# Particle-Photon-Carrier.net
KiCad netlist of a schematic drawn in EAGLE
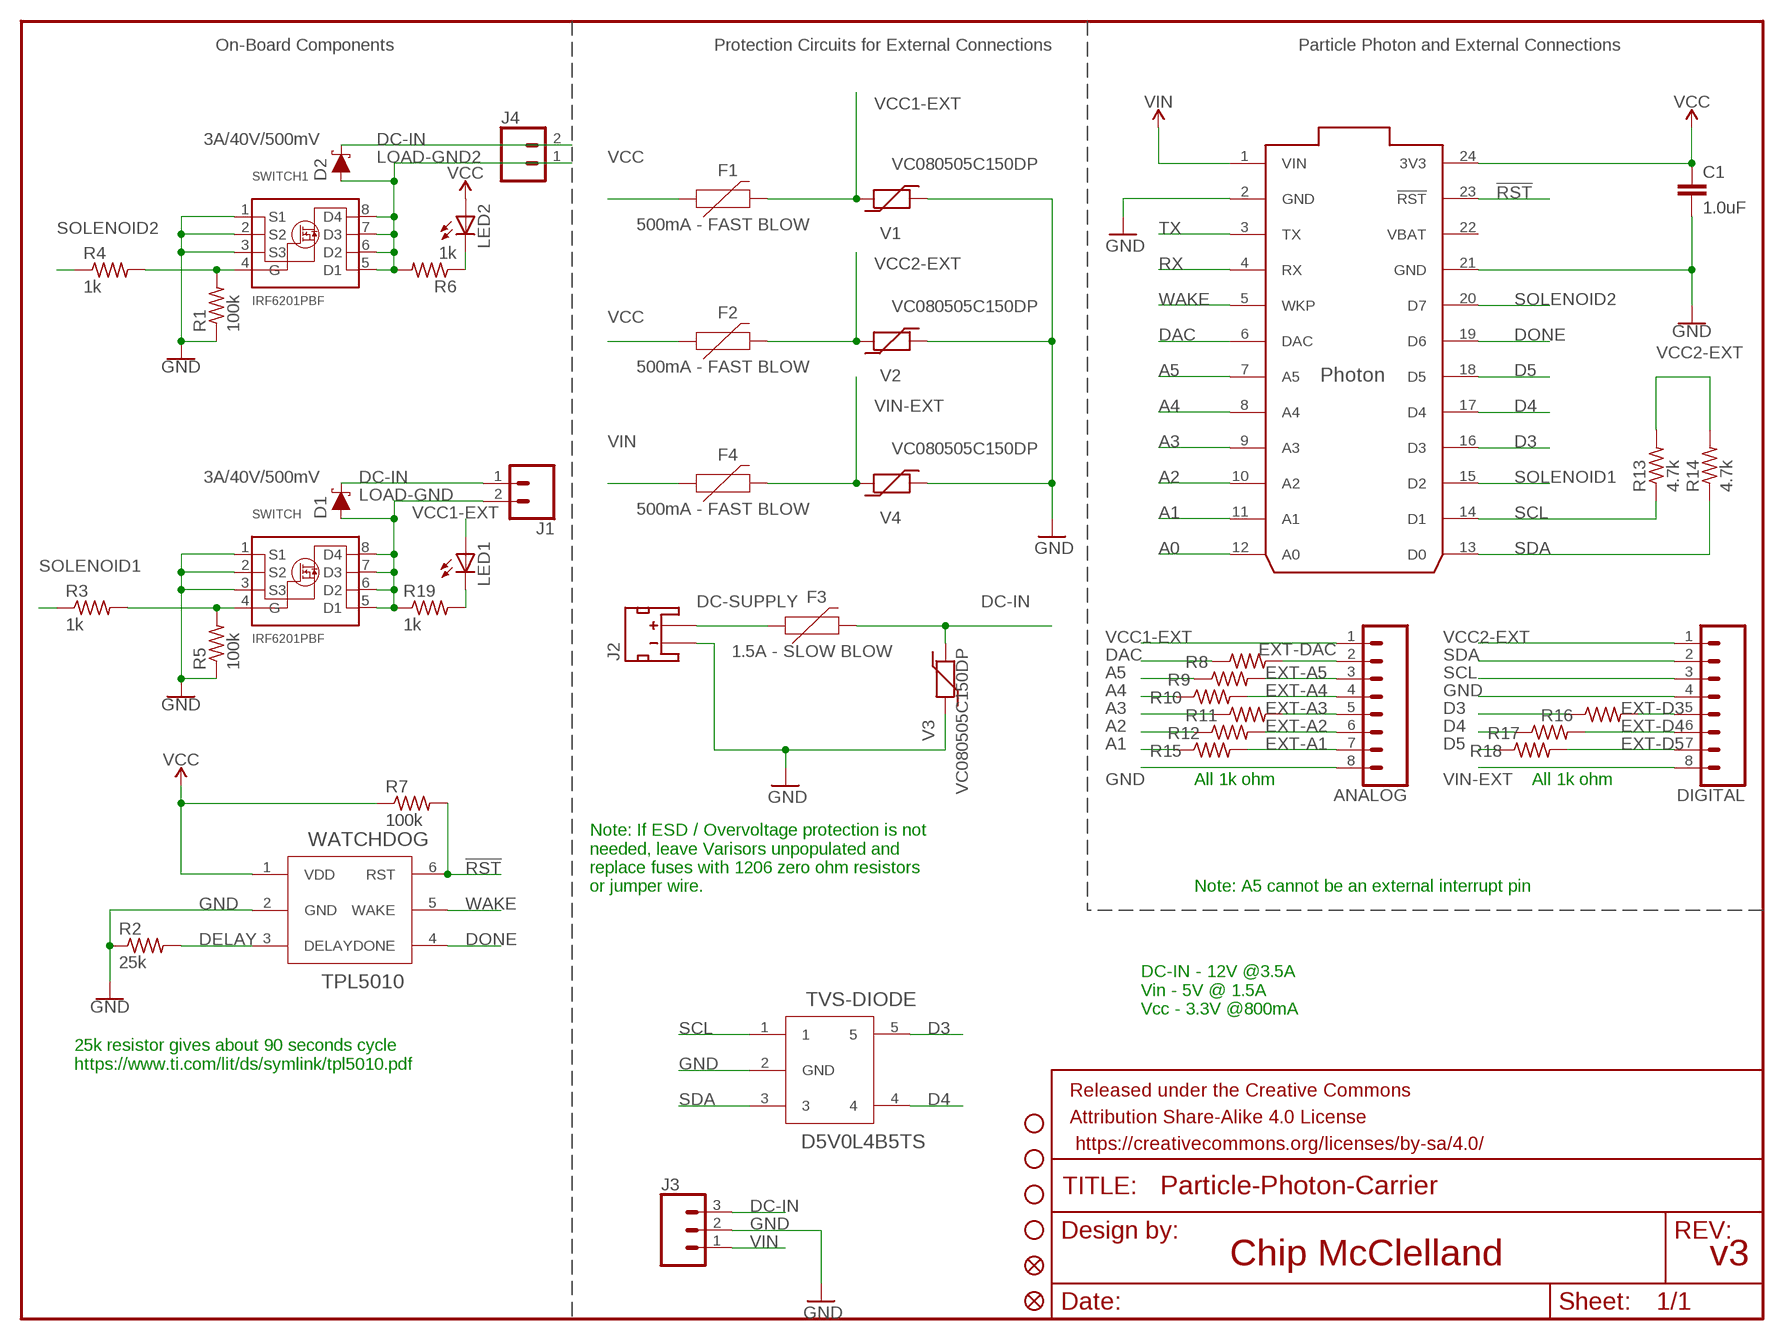
[diagram p0: schematic, sheet 1]

(export (version "E")
  (design (tool "Eeschema 10.0.6"))
  (components
    (comp (ref "ANALOG")
      (value "CONN_083.5MM-8")
      (footprint "eagle-import:SCREWTERMINAL-3.5MM-8")
      (libsource (lib "eagle-import") (part "CONN_083.5MM-8"))
    )
    (comp (ref "C1")
      (value "1.0uF")
      (footprint "eagle-import:0805")
      (libsource (lib "eagle-import") (part "1.0UF-0805-25V-10%"))
    )
    (comp (ref "D1")
      (value "3A/40V/500mV")
      (footprint "eagle-import:SMA-DIODE")
      (libsource (lib "eagle-import") (part "DIODE-SCHOTTKY-B340A"))
    )
    (comp (ref "D2")
      (value "3A/40V/500mV")
      (footprint "eagle-import:SMA-DIODE")
      (libsource (lib "eagle-import") (part "DIODE-SCHOTTKY-B340A"))
    )
    (comp (ref "DIGITAL")
      (value "CONN_083.5MM-8")
      (footprint "eagle-import:SCREWTERMINAL-3.5MM-8")
      (libsource (lib "eagle-import") (part "CONN_083.5MM-8"))
    )
    (comp (ref "F1")
      (value "500mA - FAST BLOW")
      (footprint "eagle-import:1206")
      (libsource (lib "eagle-import") (part "PPTC_HALF-AMP"))
    )
    (comp (ref "F2")
      (value "500mA - FAST BLOW")
      (footprint "eagle-import:1206")
      (libsource (lib "eagle-import") (part "PPTC_HALF-AMP"))
    )
    (comp (ref "F3")
      (value "1.5A - SLOW BLOW")
      (footprint "eagle-import:1206")
      (libsource (lib "eagle-import") (part "PPTC_HALF-AMP"))
    )
    (comp (ref "F4")
      (value "500mA - FAST BLOW")
      (footprint "eagle-import:1206")
      (libsource (lib "eagle-import") (part "PPTC_HALF-AMP"))
    )
    (comp (ref "FD1")
      (value "FIDUCIALUFIDUCIAL")
      (footprint "eagle-import:FIDUCIAL-MICRO")
      (libsource (lib "eagle-import") (part "FIDUCIALUFIDUCIAL"))
    )
    (comp (ref "FD2")
      (value "FIDUCIALUFIDUCIAL")
      (footprint "eagle-import:FIDUCIAL-MICRO")
      (libsource (lib "eagle-import") (part "FIDUCIALUFIDUCIAL"))
    )
    (comp (ref "FRAME1")
      (value "FRAME-LETTER")
      (footprint "eagle-import:CREATIVE_COMMONS")
      (libsource (lib "eagle-import") (part "FRAME-LETTER"))
    )
    (comp (ref "J1")
      (value "CONN_023.5MM")
      (footprint "eagle-import:SCREWTERMINAL-3.5MM-2")
      (libsource (lib "eagle-import") (part "CONN_023.5MM"))
    )
    (comp (ref "J2")
      (value "5V @ 2A")
      (footprint "eagle-import:JST-2-SMD")
      (libsource (lib "eagle-import") (part "JST_2MM_MALE"))
    )
    (comp (ref "J3")
      (value "CONN_03LOCK")
      (footprint "eagle-import:1X03_LOCK")
      (libsource (lib "eagle-import") (part "CONN_03LOCK"))
    )
    (comp (ref "J4")
      (value "CONN_023.5MM")
      (footprint "eagle-import:SCREWTERMINAL-3.5MM-2")
      (libsource (lib "eagle-import") (part "CONN_023.5MM"))
    )
    (comp (ref "JP3")
      (value "STAND-OFF")
      (footprint "eagle-import:STAND-OFF")
      (libsource (lib "eagle-import") (part "STAND-OFF"))
    )
    (comp (ref "JP4")
      (value "STAND-OFF")
      (footprint "eagle-import:STAND-OFF")
      (libsource (lib "eagle-import") (part "STAND-OFF"))
    )
    (comp (ref "JP5")
      (value "STAND-OFF")
      (footprint "eagle-import:STAND-OFF")
      (libsource (lib "eagle-import") (part "STAND-OFF"))
    )
    (comp (ref "JP6")
      (value "STAND-OFF")
      (footprint "eagle-import:STAND-OFF")
      (libsource (lib "eagle-import") (part "STAND-OFF"))
    )
    (comp (ref "LED1")
      (value "LEDCHIPLED_0805")
      (footprint "eagle-import:CHIPLED_0805")
      (libsource (lib "eagle-import") (part "LEDCHIPLED_0805"))
    )
    (comp (ref "LED2")
      (value "LEDCHIPLED_0805")
      (footprint "eagle-import:CHIPLED_0805")
      (libsource (lib "eagle-import") (part "LEDCHIPLED_0805"))
    )
    (comp (ref "PHOTON")
      (value "PHOTON_WITH_HEADERS")
      (footprint "eagle-import:PHOTON")
      (libsource (lib "eagle-import") (part "PHOTON_WITH_HEADERS"))
    )
    (comp (ref "R1")
      (value "100k")
      (footprint "eagle-import:R0805")
      (libsource (lib "eagle-import") (part "R-US_R0805"))
    )
    (comp (ref "R2")
      (value "25k")
      (footprint "eagle-import:R0805")
      (libsource (lib "eagle-import") (part "R-US_R0805"))
    )
    (comp (ref "R3")
      (value "1k")
      (footprint "eagle-import:R0805")
      (libsource (lib "eagle-import") (part "R-US_R0805"))
    )
    (comp (ref "R4")
      (value "1k")
      (footprint "eagle-import:R0805")
      (libsource (lib "eagle-import") (part "R-US_R0805"))
    )
    (comp (ref "R5")
      (value "100k")
      (footprint "eagle-import:R0805")
      (libsource (lib "eagle-import") (part "R-US_R0805"))
    )
    (comp (ref "R6")
      (value "1k")
      (footprint "eagle-import:R0805")
      (libsource (lib "eagle-import") (part "R-US_R0805"))
    )
    (comp (ref "R7")
      (value "100k")
      (footprint "eagle-import:R0805")
      (libsource (lib "eagle-import") (part "R-US_R0805"))
    )
    (comp (ref "R8")
      (value "1k")
      (footprint "eagle-import:R0805")
      (libsource (lib "eagle-import") (part "R-US_R0805"))
    )
    (comp (ref "R9")
      (value "1k")
      (footprint "eagle-import:R0805")
      (libsource (lib "eagle-import") (part "R-US_R0805"))
    )
    (comp (ref "R10")
      (value "1k")
      (footprint "eagle-import:R0805")
      (libsource (lib "eagle-import") (part "R-US_R0805"))
    )
    (comp (ref "R11")
      (value "1k")
      (footprint "eagle-import:R0805")
      (libsource (lib "eagle-import") (part "R-US_R0805"))
    )
    (comp (ref "R12")
      (value "1k")
      (footprint "eagle-import:R0805")
      (libsource (lib "eagle-import") (part "R-US_R0805"))
    )
    (comp (ref "R13")
      (value "4.7k")
      (footprint "eagle-import:R0805")
      (libsource (lib "eagle-import") (part "R-US_R0805"))
    )
    (comp (ref "R14")
      (value "4.7k")
      (footprint "eagle-import:R0805")
      (libsource (lib "eagle-import") (part "R-US_R0805"))
    )
    (comp (ref "R15")
      (value "1k")
      (footprint "eagle-import:R0805")
      (libsource (lib "eagle-import") (part "R-US_R0805"))
    )
    (comp (ref "R16")
      (value "1k")
      (footprint "eagle-import:R0805")
      (libsource (lib "eagle-import") (part "R-US_R0805"))
    )
    (comp (ref "R17")
      (value "1k")
      (footprint "eagle-import:R0805")
      (libsource (lib "eagle-import") (part "R-US_R0805"))
    )
    (comp (ref "R18")
      (value "1k")
      (footprint "eagle-import:R0805")
      (libsource (lib "eagle-import") (part "R-US_R0805"))
    )
    (comp (ref "R19")
      (value "1k")
      (footprint "eagle-import:R0805")
      (libsource (lib "eagle-import") (part "R-US_R0805"))
    )
    (comp (ref "SWITCH")
      (value "IRF6201PBF")
      (footprint "eagle-import:SO8-GW300")
      (libsource (lib "eagle-import") (part "IRF6201PBF"))
    )
    (comp (ref "SWITCH1")
      (value "IRF6201PBF")
      (footprint "eagle-import:SO8-GW300")
      (libsource (lib "eagle-import") (part "IRF6201PBF"))
    )
    (comp (ref "TVS-DIODE")
      (value "D5V0L4B5TS")
      (footprint "eagle-import:SOT-23-5")
      (libsource (lib "eagle-import") (part "D5V0L4B5TS"))
    )
    (comp (ref "V1")
      (value "VC080505C150DP")
      (footprint "eagle-import:0805")
      (libsource (lib "eagle-import") (part "VARISTOR"))
    )
    (comp (ref "V2")
      (value "VC080505C150DP")
      (footprint "eagle-import:0805")
      (libsource (lib "eagle-import") (part "VARISTOR"))
    )
    (comp (ref "V3")
      (value "VC080505C150DP")
      (footprint "eagle-import:0805")
      (libsource (lib "eagle-import") (part "VARISTOR"))
    )
    (comp (ref "V4")
      (value "VC080505C150DP")
      (footprint "eagle-import:0805")
      (libsource (lib "eagle-import") (part "VARISTOR"))
    )
    (comp (ref "WATCHDOG")
      (value "TPL5010")
      (footprint "eagle-import:TSOT-23")
      (libsource (lib "eagle-import") (part "TPL5010"))
    )
  )
  (nets
    (net (code "1") (name "/A0") (class "Default")
      (node (ref "PHOTON") (pin "12") (pinfunction "A0_12") (pintype "bidirectional"))
    )
    (net (code "2") (name "/A1") (class "Default")
      (node (ref "PHOTON") (pin "11") (pinfunction "A1_11") (pintype "bidirectional"))
      (node (ref "R15") (pin "1") (pinfunction "1_1") (pintype "passive"))
    )
    (net (code "3") (name "/A2") (class "Default")
      (node (ref "PHOTON") (pin "10") (pinfunction "A2_10") (pintype "bidirectional"))
      (node (ref "R12") (pin "1") (pinfunction "1_1") (pintype "passive"))
    )
    (net (code "4") (name "/A3") (class "Default")
      (node (ref "PHOTON") (pin "9") (pinfunction "A3_9") (pintype "bidirectional"))
      (node (ref "R11") (pin "1") (pinfunction "1_1") (pintype "passive"))
    )
    (net (code "5") (name "/A4") (class "Default")
      (node (ref "PHOTON") (pin "8") (pinfunction "A4_8") (pintype "bidirectional"))
      (node (ref "R10") (pin "1") (pinfunction "1_1") (pintype "passive"))
    )
    (net (code "6") (name "/A5") (class "Default")
      (node (ref "PHOTON") (pin "7") (pinfunction "A5_7") (pintype "bidirectional"))
      (node (ref "R9") (pin "1") (pinfunction "1_1") (pintype "passive"))
    )
    (net (code "7") (name "/D3") (class "Default")
      (node (ref "PHOTON") (pin "16") (pinfunction "D3_16") (pintype "bidirectional"))
      (node (ref "R16") (pin "1") (pinfunction "1_1") (pintype "passive"))
      (node (ref "TVS-DIODE") (pin "5") (pinfunction "5_5") (pintype "power_in"))
    )
    (net (code "8") (name "/D4") (class "Default")
      (node (ref "PHOTON") (pin "17") (pinfunction "D4_17") (pintype "bidirectional"))
      (node (ref "R17") (pin "1") (pinfunction "1_1") (pintype "passive"))
      (node (ref "TVS-DIODE") (pin "4") (pinfunction "4_4") (pintype "input"))
    )
    (net (code "9") (name "/D5") (class "Default")
      (node (ref "PHOTON") (pin "18") (pinfunction "D5_18") (pintype "bidirectional"))
      (node (ref "R18") (pin "1") (pinfunction "1_1") (pintype "passive"))
    )
    (net (code "10") (name "/DAC") (class "Default")
      (node (ref "PHOTON") (pin "6") (pinfunction "DAC_6") (pintype "bidirectional"))
      (node (ref "R8") (pin "1") (pinfunction "1_1") (pintype "passive"))
    )
    (net (code "11") (name "/DC-IN") (class "Default")
      (node (ref "D1") (pin "C") (pinfunction "C_C") (pintype "passive"))
      (node (ref "D2") (pin "C") (pinfunction "C_C") (pintype "passive"))
      (node (ref "F3") (pin "2") (pinfunction "2_2") (pintype "bidirectional"))
      (node (ref "J1") (pin "1") (pinfunction "1_1") (pintype "passive"))
      (node (ref "J3") (pin "3") (pinfunction "3_3") (pintype "passive"))
      (node (ref "J4") (pin "2") (pinfunction "2_2") (pintype "passive"))
      (node (ref "V3") (pin "2") (pinfunction "2_2") (pintype "passive"))
    )
    (net (code "12") (name "/DC-SUPPLY") (class "Default")
      (node (ref "F3") (pin "1") (pinfunction "1_1") (pintype "bidirectional"))
      (node (ref "J2") (pin "2") (pinfunction "+_2") (pintype "bidirectional"))
    )
    (net (code "13") (name "/DELAY") (class "Default")
      (node (ref "R2") (pin "2") (pinfunction "2_2") (pintype "passive"))
      (node (ref "WATCHDOG") (pin "3") (pinfunction "DELAY_3") (pintype "power_in"))
    )
    (net (code "14") (name "/DONE") (class "Default")
      (node (ref "PHOTON") (pin "19") (pinfunction "D6_19") (pintype "bidirectional"))
      (node (ref "WATCHDOG") (pin "4") (pinfunction "DONE_4") (pintype "input"))
    )
    (net (code "15") (name "/EXT-A1") (class "Default")
      (node (ref "ANALOG") (pin "7") (pinfunction "7_7") (pintype "passive"))
      (node (ref "R15") (pin "2") (pinfunction "2_2") (pintype "passive"))
    )
    (net (code "16") (name "/EXT-A2") (class "Default")
      (node (ref "ANALOG") (pin "6") (pinfunction "6_6") (pintype "passive"))
      (node (ref "R12") (pin "2") (pinfunction "2_2") (pintype "passive"))
    )
    (net (code "17") (name "/EXT-A3") (class "Default")
      (node (ref "ANALOG") (pin "5") (pinfunction "5_5") (pintype "passive"))
      (node (ref "R11") (pin "2") (pinfunction "2_2") (pintype "passive"))
    )
    (net (code "18") (name "/EXT-A4") (class "Default")
      (node (ref "ANALOG") (pin "4") (pinfunction "4_4") (pintype "passive"))
      (node (ref "R10") (pin "2") (pinfunction "2_2") (pintype "passive"))
    )
    (net (code "19") (name "/EXT-A5") (class "Default")
      (node (ref "ANALOG") (pin "3") (pinfunction "3_3") (pintype "passive"))
      (node (ref "R9") (pin "2") (pinfunction "2_2") (pintype "passive"))
    )
    (net (code "20") (name "/EXT-D3") (class "Default")
      (node (ref "DIGITAL") (pin "5") (pinfunction "5_5") (pintype "passive"))
      (node (ref "R16") (pin "2") (pinfunction "2_2") (pintype "passive"))
    )
    (net (code "21") (name "/EXT-D4") (class "Default")
      (node (ref "DIGITAL") (pin "6") (pinfunction "6_6") (pintype "passive"))
      (node (ref "R17") (pin "2") (pinfunction "2_2") (pintype "passive"))
    )
    (net (code "22") (name "/EXT-D5") (class "Default")
      (node (ref "DIGITAL") (pin "7") (pinfunction "7_7") (pintype "passive"))
      (node (ref "R18") (pin "2") (pinfunction "2_2") (pintype "passive"))
    )
    (net (code "23") (name "/EXT-DAC") (class "Default")
      (node (ref "ANALOG") (pin "2") (pinfunction "2_2") (pintype "passive"))
      (node (ref "R8") (pin "2") (pinfunction "2_2") (pintype "passive"))
    )
    (net (code "24") (name "/LOAD-GND") (class "Default")
      (node (ref "D1") (pin "A") (pinfunction "A_A") (pintype "passive"))
      (node (ref "J1") (pin "2") (pinfunction "2_2") (pintype "passive"))
      (node (ref "R19") (pin "1") (pinfunction "1_1") (pintype "passive"))
      (node (ref "SWITCH") (pin "5") (pinfunction "D1_5") (pintype "bidirectional"))
      (node (ref "SWITCH") (pin "6") (pinfunction "D2_6") (pintype "bidirectional"))
      (node (ref "SWITCH") (pin "7") (pinfunction "D3_7") (pintype "bidirectional"))
      (node (ref "SWITCH") (pin "8") (pinfunction "D4_8") (pintype "bidirectional"))
    )
    (net (code "25") (name "/LOAD-GND2") (class "Default")
      (node (ref "D2") (pin "A") (pinfunction "A_A") (pintype "passive"))
      (node (ref "J4") (pin "1") (pinfunction "1_1") (pintype "passive"))
      (node (ref "R6") (pin "2") (pinfunction "2_2") (pintype "passive"))
      (node (ref "SWITCH1") (pin "5") (pinfunction "D1_5") (pintype "bidirectional"))
      (node (ref "SWITCH1") (pin "6") (pinfunction "D2_6") (pintype "bidirectional"))
      (node (ref "SWITCH1") (pin "7") (pinfunction "D3_7") (pintype "bidirectional"))
      (node (ref "SWITCH1") (pin "8") (pinfunction "D4_8") (pintype "bidirectional"))
    )
    (net (code "26") (name "/RX") (class "Default")
      (node (ref "PHOTON") (pin "4") (pinfunction "RX_4") (pintype "bidirectional"))
    )
    (net (code "27") (name "/SCL") (class "Default")
      (node (ref "DIGITAL") (pin "3") (pinfunction "3_3") (pintype "passive"))
      (node (ref "PHOTON") (pin "14") (pinfunction "D1_14") (pintype "bidirectional"))
      (node (ref "R13") (pin "1") (pinfunction "1_1") (pintype "passive"))
      (node (ref "TVS-DIODE") (pin "1") (pinfunction "1_1") (pintype "power_in"))
    )
    (net (code "28") (name "/SDA") (class "Default")
      (node (ref "DIGITAL") (pin "2") (pinfunction "2_2") (pintype "passive"))
      (node (ref "PHOTON") (pin "13") (pinfunction "D0_13") (pintype "bidirectional"))
      (node (ref "R14") (pin "1") (pinfunction "1_1") (pintype "passive"))
      (node (ref "TVS-DIODE") (pin "3") (pinfunction "3_3") (pintype "power_in"))
    )
    (net (code "29") (name "/SOLENOID1") (class "Default")
      (node (ref "PHOTON") (pin "15") (pinfunction "D2_15") (pintype "bidirectional"))
      (node (ref "R3") (pin "1") (pinfunction "1_1") (pintype "passive"))
    )
    (net (code "30") (name "/SOLENOID2") (class "Default")
      (node (ref "PHOTON") (pin "20") (pinfunction "D7_20") (pintype "bidirectional"))
      (node (ref "R4") (pin "1") (pinfunction "1_1") (pintype "passive"))
    )
    (net (code "31") (name "/TX") (class "Default")
      (node (ref "PHOTON") (pin "3") (pinfunction "TX_3") (pintype "bidirectional"))
    )
    (net (code "32") (name "/VBAT") (class "Default")
      (node (ref "PHOTON") (pin "22") (pinfunction "VBAT_22") (pintype "power_in"))
    )
    (net (code "33") (name "/VCC1-EXT") (class "Default")
      (node (ref "ANALOG") (pin "1") (pinfunction "1_1") (pintype "passive"))
      (node (ref "F1") (pin "2") (pinfunction "2_2") (pintype "bidirectional"))
      (node (ref "LED1") (pin "A") (pinfunction "A_A") (pintype "passive"))
      (node (ref "V1") (pin "2") (pinfunction "2_2") (pintype "passive"))
    )
    (net (code "34") (name "/VCC2-EXT") (class "Default")
      (node (ref "DIGITAL") (pin "1") (pinfunction "1_1") (pintype "passive"))
      (node (ref "F2") (pin "2") (pinfunction "2_2") (pintype "bidirectional"))
      (node (ref "R13") (pin "2") (pinfunction "2_2") (pintype "passive"))
      (node (ref "R14") (pin "2") (pinfunction "2_2") (pintype "passive"))
      (node (ref "V2") (pin "2") (pinfunction "2_2") (pintype "passive"))
    )
    (net (code "35") (name "/VIN-EXT") (class "Default")
      (node (ref "DIGITAL") (pin "8") (pinfunction "8_8") (pintype "passive"))
      (node (ref "F4") (pin "2") (pinfunction "2_2") (pintype "bidirectional"))
      (node (ref "V4") (pin "2") (pinfunction "2_2") (pintype "passive"))
    )
    (net (code "36") (name "/WAKE") (class "Default")
      (node (ref "PHOTON") (pin "5") (pinfunction "WKP_5") (pintype "bidirectional"))
      (node (ref "WATCHDOG") (pin "5") (pinfunction "WAKE_5") (pintype "bidirectional"))
    )
    (net (code "37") (name "/~{RST}") (class "Default")
      (node (ref "PHOTON") (pin "23") (pinfunction "~{RST}_23") (pintype "bidirectional"))
      (node (ref "R7") (pin "2") (pinfunction "2_2") (pintype "passive"))
      (node (ref "WATCHDOG") (pin "6") (pinfunction "RST_6") (pintype "power_in"))
    )
    (net (code "38") (name "GND") (class "Default")
      (node (ref "ANALOG") (pin "8") (pinfunction "8_8") (pintype "passive"))
      (node (ref "C1") (pin "2") (pinfunction "2_2") (pintype "passive"))
      (node (ref "DIGITAL") (pin "4") (pinfunction "4_4") (pintype "passive"))
      (node (ref "J2") (pin "1") (pinfunction "-_1") (pintype "bidirectional"))
      (node (ref "J3") (pin "2") (pinfunction "2_2") (pintype "passive"))
      (node (ref "PHOTON") (pin "2") (pinfunction "GND_2") (pintype "power_in"))
      (node (ref "PHOTON") (pin "21") (pinfunction "GND_21") (pintype "power_in"))
      (node (ref "R1") (pin "1") (pinfunction "1_1") (pintype "passive"))
      (node (ref "R2") (pin "1") (pinfunction "1_1") (pintype "passive"))
      (node (ref "R5") (pin "1") (pinfunction "1_1") (pintype "passive"))
      (node (ref "SWITCH") (pin "1") (pinfunction "S1_1") (pintype "bidirectional"))
      (node (ref "SWITCH") (pin "2") (pinfunction "S2_2") (pintype "bidirectional"))
      (node (ref "SWITCH") (pin "3") (pinfunction "S3_3") (pintype "bidirectional"))
      (node (ref "SWITCH1") (pin "1") (pinfunction "S1_1") (pintype "bidirectional"))
      (node (ref "SWITCH1") (pin "2") (pinfunction "S2_2") (pintype "bidirectional"))
      (node (ref "SWITCH1") (pin "3") (pinfunction "S3_3") (pintype "bidirectional"))
      (node (ref "TVS-DIODE") (pin "2") (pinfunction "GND_2") (pintype "input"))
      (node (ref "V1") (pin "1") (pinfunction "1_1") (pintype "passive"))
      (node (ref "V2") (pin "1") (pinfunction "1_1") (pintype "passive"))
      (node (ref "V3") (pin "1") (pinfunction "1_1") (pintype "passive"))
      (node (ref "V4") (pin "1") (pinfunction "1_1") (pintype "passive"))
      (node (ref "WATCHDOG") (pin "2") (pinfunction "GND_2") (pintype "input"))
    )
    (net (code "39") (name "Net-(LED1-PadC)") (class "Default")
      (node (ref "LED1") (pin "C") (pinfunction "C_C") (pintype "passive"))
      (node (ref "R19") (pin "2") (pinfunction "2_2") (pintype "passive"))
    )
    (net (code "40") (name "Net-(LED2-PadC)") (class "Default")
      (node (ref "LED2") (pin "C") (pinfunction "C_C") (pintype "passive"))
      (node (ref "R6") (pin "1") (pinfunction "1_1") (pintype "passive"))
    )
    (net (code "41") (name "Net-(SWITCH-G)") (class "Default")
      (node (ref "R3") (pin "2") (pinfunction "2_2") (pintype "passive"))
      (node (ref "R5") (pin "2") (pinfunction "2_2") (pintype "passive"))
      (node (ref "SWITCH") (pin "4") (pinfunction "G_4") (pintype "bidirectional"))
    )
    (net (code "42") (name "Net-(SWITCH1-G)") (class "Default")
      (node (ref "R1") (pin "2") (pinfunction "2_2") (pintype "passive"))
      (node (ref "R4") (pin "2") (pinfunction "2_2") (pintype "passive"))
      (node (ref "SWITCH1") (pin "4") (pinfunction "G_4") (pintype "bidirectional"))
    )
    (net (code "43") (name "VCC") (class "Default")
      (node (ref "C1") (pin "1") (pinfunction "1_1") (pintype "passive"))
      (node (ref "F1") (pin "1") (pinfunction "1_1") (pintype "bidirectional"))
      (node (ref "F2") (pin "1") (pinfunction "1_1") (pintype "bidirectional"))
      (node (ref "LED2") (pin "A") (pinfunction "A_A") (pintype "passive"))
      (node (ref "PHOTON") (pin "24") (pinfunction "3V3_24") (pintype "power_in"))
      (node (ref "R7") (pin "1") (pinfunction "1_1") (pintype "passive"))
      (node (ref "WATCHDOG") (pin "1") (pinfunction "VDD_1") (pintype "power_in"))
    )
    (net (code "44") (name "VIN") (class "Default")
      (node (ref "F4") (pin "1") (pinfunction "1_1") (pintype "bidirectional"))
      (node (ref "J3") (pin "1") (pinfunction "1_1") (pintype "passive"))
      (node (ref "PHOTON") (pin "1") (pinfunction "VIN_1") (pintype "power_in"))
    )
    (net (code "45") (name "unconnected-(J2-PAD1-PadNC1)") (class "Default")
      (node (ref "J2") (pin "NC1") (pinfunction "PAD1_NC1") (pintype "bidirectional"))
    )
    (net (code "46") (name "unconnected-(J2-PAD2-PadNC2)") (class "Default")
      (node (ref "J2") (pin "NC2") (pinfunction "PAD2_NC2") (pintype "bidirectional"))
    )
  )
)
